# vbus_v2.net
KiCad netlist of a schematic drawn in EAGLE
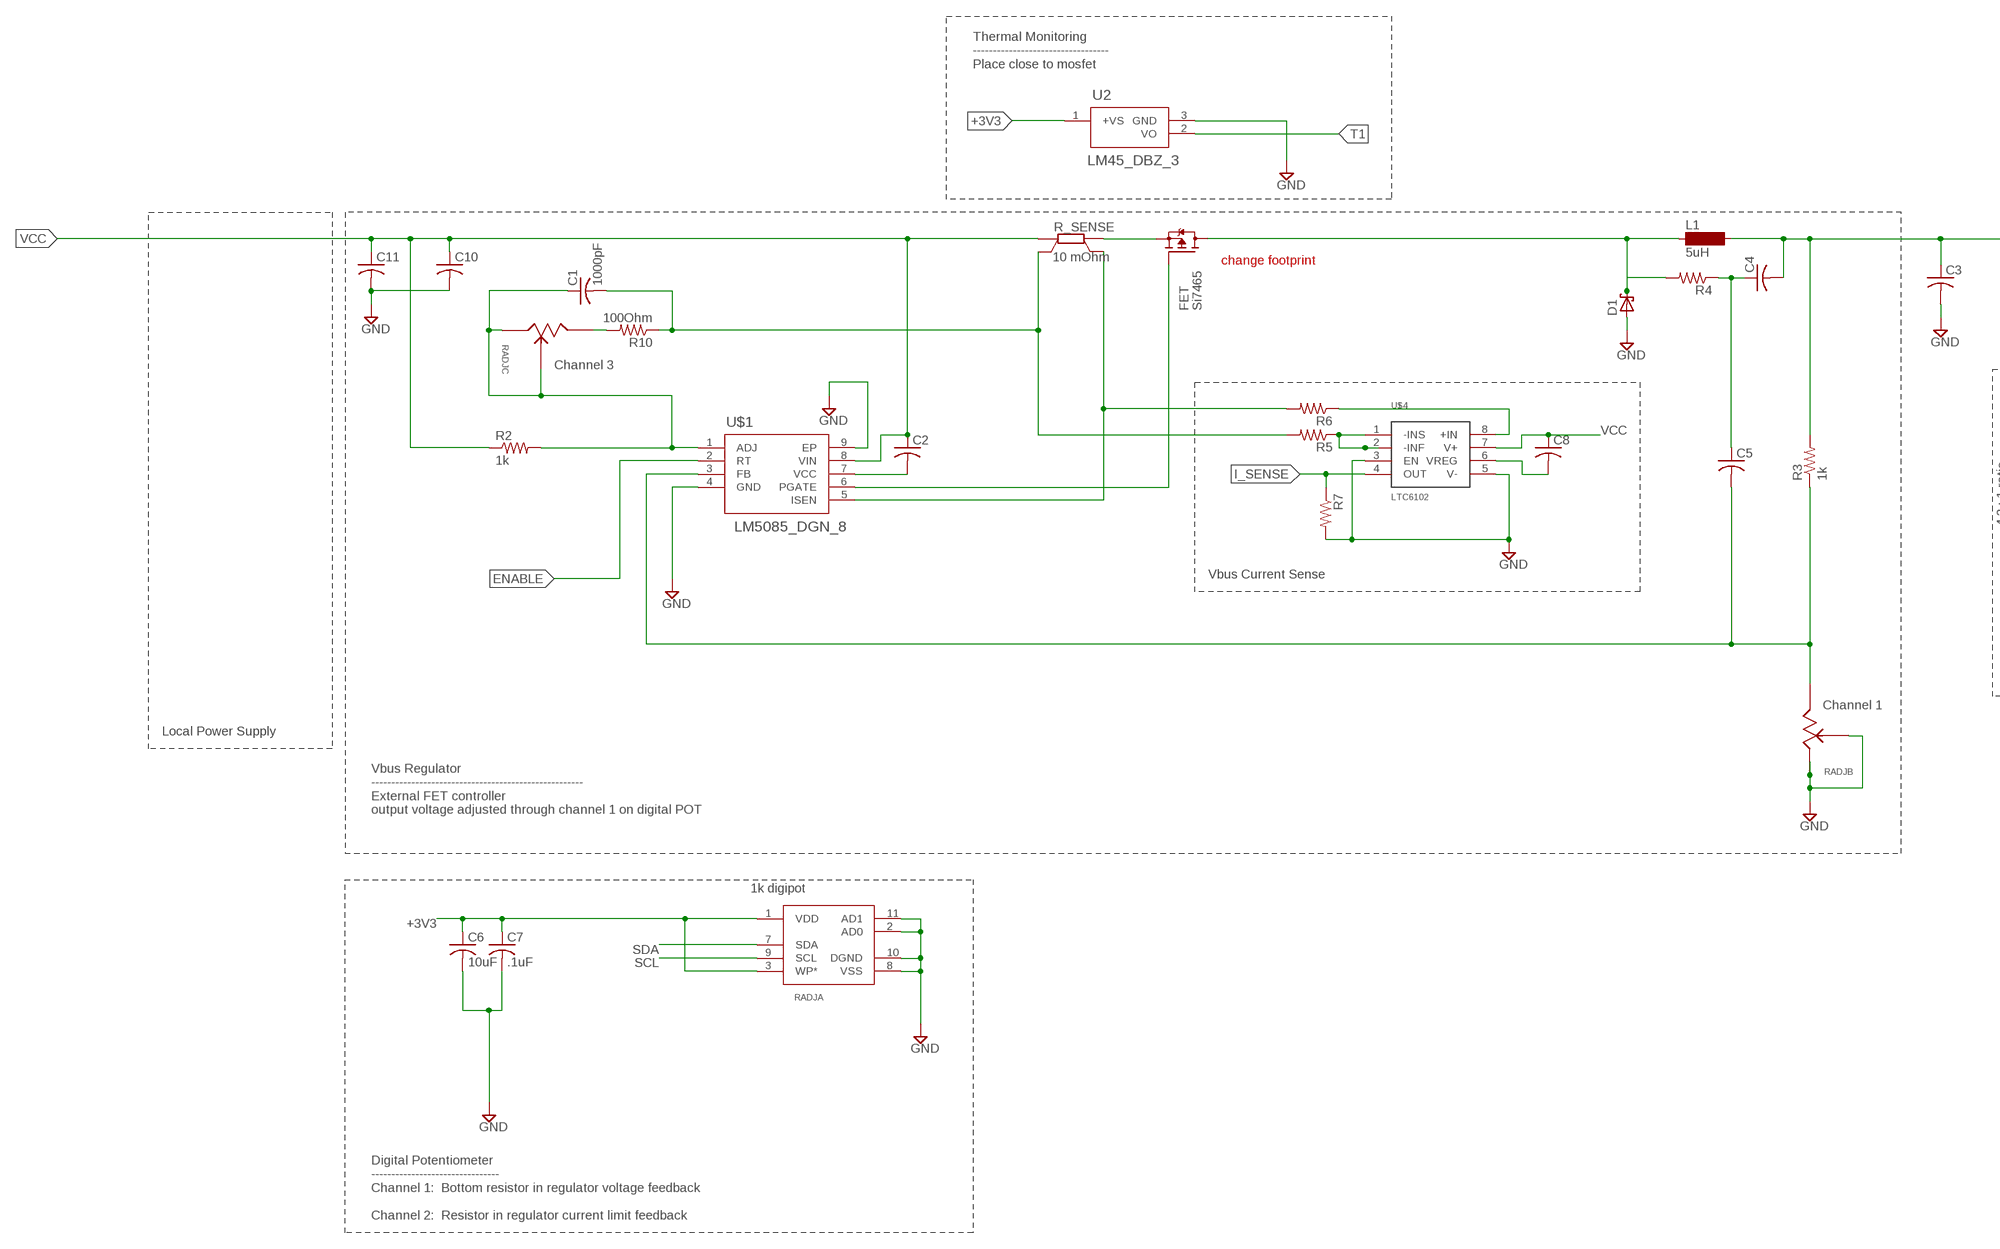
[diagram p0: schematic, sheet 1, part 1 of 2]
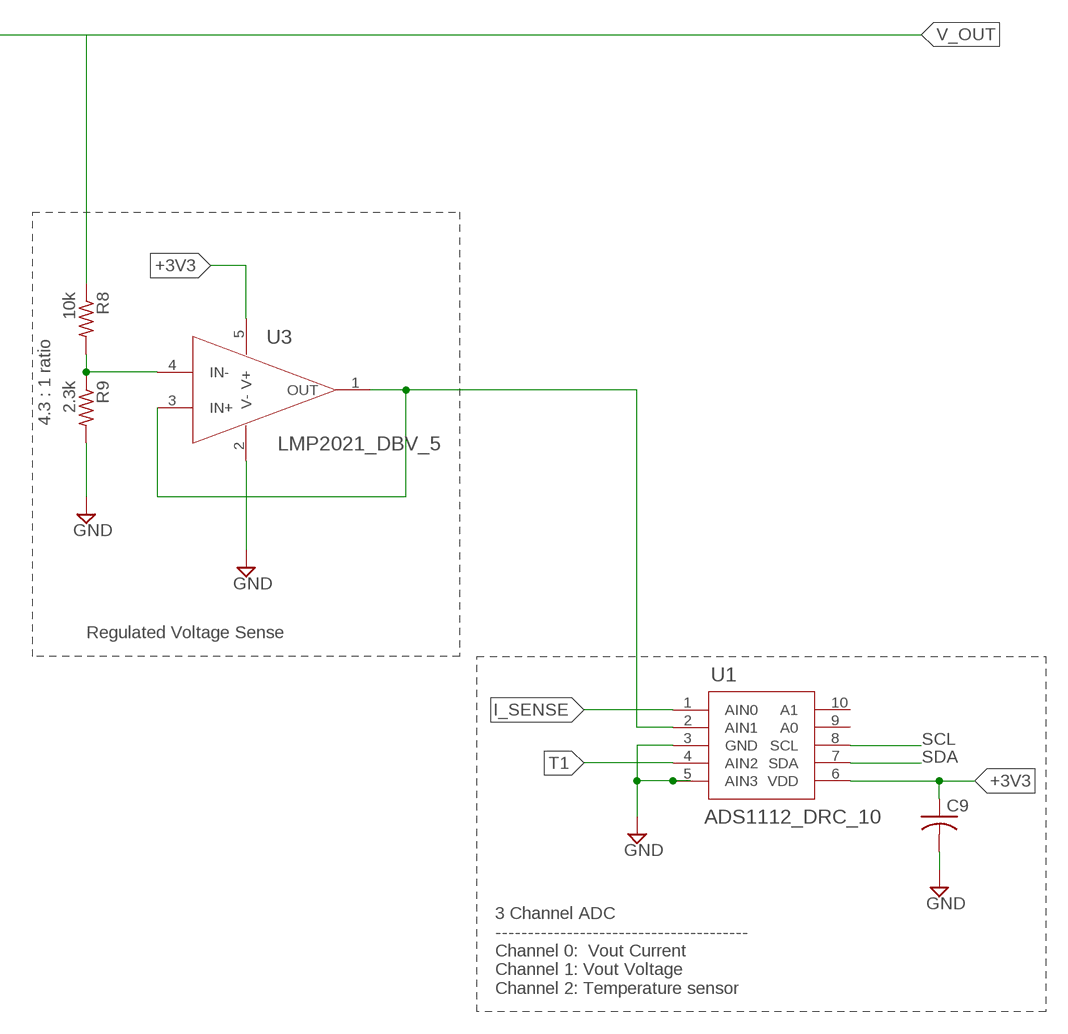
[diagram p1: schematic, sheet 1, part 2 of 2]

(export (version "E")
  (design (tool "Eeschema 10.0.6"))
  (components
    (comp (ref "C1")
      (value "1000pF")
      (footprint "eagle-import:C0805")
      (libsource (lib "eagle-import") (part "C-USC0805"))
    )
    (comp (ref "C2")
      (value "C-USC0805")
      (footprint "eagle-import:C0805")
      (libsource (lib "eagle-import") (part "C-USC0805"))
    )
    (comp (ref "C3")
      (value "C-USC0805")
      (footprint "eagle-import:C0805")
      (libsource (lib "eagle-import") (part "C-USC0805"))
    )
    (comp (ref "C4")
      (value "C-USC0805")
      (footprint "eagle-import:C0805")
      (libsource (lib "eagle-import") (part "C-USC0805"))
    )
    (comp (ref "C5")
      (value "C-USC0805")
      (footprint "eagle-import:C0805")
      (libsource (lib "eagle-import") (part "C-USC0805"))
    )
    (comp (ref "C6")
      (value "10uF")
      (footprint "eagle-import:C0805")
      (libsource (lib "eagle-import") (part "C-USC0805"))
    )
    (comp (ref "C7")
      (value ".1uF")
      (footprint "eagle-import:C0805")
      (libsource (lib "eagle-import") (part "C-USC0805"))
    )
    (comp (ref "C8")
      (value "C-USC0805")
      (footprint "eagle-import:C0805")
      (libsource (lib "eagle-import") (part "C-USC0805"))
    )
    (comp (ref "C9")
      (value "C-USC0805")
      (footprint "eagle-import:C0805")
      (libsource (lib "eagle-import") (part "C-USC0805"))
    )
    (comp (ref "C10")
      (value "C-USC0805")
      (footprint "eagle-import:C0805")
      (libsource (lib "eagle-import") (part "C-USC0805"))
    )
    (comp (ref "C11")
      (value "C-USC0805")
      (footprint "eagle-import:C0805")
      (libsource (lib "eagle-import") (part "C-USC0805"))
    )
    (comp (ref "D1")
      (value "SCHOTTKY-DIODETO92H")
      (footprint "eagle-import:TO92H")
      (libsource (lib "eagle-import") (part "SCHOTTKY-DIODETO92H"))
    )
    (comp (ref "FET")
      (value "Si7465")
      (footprint "eagle-import:SOT-223")
      (libsource (lib "eagle-import") (part "FDT434P"))
    )
    (comp (ref "L1")
      (value "5uH")
      (footprint "eagle-import:MS50")
      (libsource (lib "eagle-import") (part "MS50"))
    )
    (comp (ref "R2")
      (value "1k")
      (footprint "eagle-import:M0805")
      (libsource (lib "eagle-import") (part "R-US_M0805"))
    )
    (comp (ref "R3")
      (value "1k")
      (footprint "eagle-import:M0805")
      (libsource (lib "eagle-import") (part "R-US_M0805"))
    )
    (comp (ref "R4")
      (value "R-US_M0805")
      (footprint "eagle-import:M0805")
      (libsource (lib "eagle-import") (part "R-US_M0805"))
    )
    (comp (ref "R5")
      (value "R-US_M0805")
      (footprint "eagle-import:M0805")
      (libsource (lib "eagle-import") (part "R-US_M0805"))
    )
    (comp (ref "R6")
      (value "R-US_M0805")
      (footprint "eagle-import:M0805")
      (libsource (lib "eagle-import") (part "R-US_M0805"))
    )
    (comp (ref "R7")
      (value "R-US_M0805")
      (footprint "eagle-import:M0805")
      (libsource (lib "eagle-import") (part "R-US_M0805"))
    )
    (comp (ref "R8")
      (value "10k")
      (footprint "eagle-import:M0805")
      (libsource (lib "eagle-import") (part "R-US_M0805"))
    )
    (comp (ref "R9")
      (value "2.3k")
      (footprint "eagle-import:M0805")
      (libsource (lib "eagle-import") (part "R-US_M0805"))
    )
    (comp (ref "R10")
      (value "100Ohm")
      (footprint "eagle-import:M0805")
      (libsource (lib "eagle-import") (part "R-US_M0805"))
    )
    (comp (ref "RADJ")
      (value "AD5252")
      (footprint "eagle-import:RU_14")
      (libsource (lib "eagle-import") (part "AD5252"))
    )
    (comp (ref "R_SENSE")
      (value "10 mOhm")
      (footprint "eagle-import:SMV")
      (libsource (lib "eagle-import") (part "SMV"))
    )
    (comp (ref "U$1")
      (value "LM5085_DGN_8")
      (footprint "eagle-import:MUY08A")
      (fields (field (name "MANUFACTURER_PART_NUMBER") "lm5085mynopb"))
      (libsource (lib "eagle-import") (part "LM5085_DGN_8"))
    )
    (comp (ref "U$4")
      (value "LTC6102")
      (footprint "eagle-import:MS8")
      (libsource (lib "eagle-import") (part "LTC6102"))
    )
    (comp (ref "U1")
      (value "ADS1112_DRC_10")
      (footprint "eagle-import:DG6-10")
      (libsource (lib "eagle-import") (part "ADS1112_DRC_10"))
    )
    (comp (ref "U2")
      (value "LM45_DBZ_3")
      (footprint "eagle-import:MF03A")
      (fields (field (name "PARTNUMBER") "LM45BIM3"))
      (libsource (lib "eagle-import") (part "LM45_DBZ_3"))
    )
    (comp (ref "U3")
      (value "LMP2021_DBV_5")
      (footprint "eagle-import:MF05A")
      (libsource (lib "eagle-import") (part "LMP2021_DBV_5"))
    )
  )
  (nets
    (net (code "1") (name "+3V3") (class "Default")
      (node (ref "C6") (pin "1") (pinfunction "1_1") (pintype "passive"))
      (node (ref "C7") (pin "1") (pinfunction "1_1") (pintype "passive"))
      (node (ref "C9") (pin "1") (pinfunction "1_1") (pintype "passive"))
      (node (ref "RADJ") (pin "1") (pinfunction "VDD_1") (pintype "power_in"))
      (node (ref "RADJ") (pin "3") (pinfunction "WP*_3") (pintype "passive"))
      (node (ref "U1") (pin "6") (pinfunction "VDD_6") (pintype "power_in"))
      (node (ref "U2") (pin "1") (pinfunction "+VS_1") (pintype "input"))
      (node (ref "U3") (pin "5") (pinfunction "V+_5") (pintype "power_in"))
    )
    (net (code "2") (name "/SCL") (class "Default")
      (node (ref "RADJ") (pin "9") (pinfunction "SCL_9") (pintype "passive"))
      (node (ref "U1") (pin "8") (pinfunction "SCL_8") (pintype "output"))
    )
    (net (code "3") (name "/SDA") (class "Default")
      (node (ref "RADJ") (pin "7") (pinfunction "SDA_7") (pintype "passive"))
      (node (ref "U1") (pin "7") (pinfunction "SDA_7") (pintype "passive"))
    )
    (net (code "4") (name "ENABLE") (class "Default")
      (node (ref "U$1") (pin "2") (pinfunction "RT_2") (pintype "passive"))
    )
    (net (code "5") (name "GND") (class "Default")
      (node (ref "C10") (pin "2") (pinfunction "2_2") (pintype "passive"))
      (node (ref "C11") (pin "2") (pinfunction "2_2") (pintype "passive"))
      (node (ref "C3") (pin "2") (pinfunction "2_2") (pintype "passive"))
      (node (ref "C6") (pin "2") (pinfunction "2_2") (pintype "passive"))
      (node (ref "C7") (pin "2") (pinfunction "2_2") (pintype "passive"))
      (node (ref "C9") (pin "2") (pinfunction "2_2") (pintype "passive"))
      (node (ref "D1") (pin "1") (pinfunction "A_1") (pintype "passive"))
      (node (ref "R7") (pin "2") (pinfunction "2_2") (pintype "passive"))
      (node (ref "R9") (pin "2") (pinfunction "2_2") (pintype "passive"))
      (node (ref "RADJ") (pin "10") (pinfunction "DGND_10") (pintype "passive"))
      (node (ref "RADJ") (pin "11") (pinfunction "AD1_11") (pintype "passive"))
      (node (ref "RADJ") (pin "2") (pinfunction "AD0_2") (pintype "passive"))
      (node (ref "RADJ") (pin "4") (pinfunction "W1_4") (pintype "passive"))
      (node (ref "RADJ") (pin "5") (pinfunction "B1_5") (pintype "passive"))
      (node (ref "RADJ") (pin "8") (pinfunction "VSS_8") (pintype "power_in"))
      (node (ref "U$1") (pin "4") (pinfunction "GND_4") (pintype "power_in"))
      (node (ref "U$1") (pin "9") (pinfunction "EP_9") (pintype "passive"))
      (node (ref "U$4") (pin "3") (pinfunction "EN_3") (pintype "power_in"))
      (node (ref "U$4") (pin "5") (pinfunction "V-_5") (pintype "power_in"))
      (node (ref "U1") (pin "3") (pinfunction "GND_3") (pintype "power_in"))
      (node (ref "U1") (pin "5") (pinfunction "AIN3_5") (pintype "input"))
      (node (ref "U2") (pin "3") (pinfunction "GND_3") (pintype "passive"))
      (node (ref "U3") (pin "2") (pinfunction "V-_2") (pintype "power_in"))
    )
    (net (code "6") (name "I_SENSE") (class "Default")
      (node (ref "R7") (pin "1") (pinfunction "1_1") (pintype "passive"))
      (node (ref "U$4") (pin "4") (pinfunction "OUT_4") (pintype "power_in"))
      (node (ref "U1") (pin "1") (pinfunction "AIN0_1") (pintype "input"))
    )
    (net (code "7") (name "Net-(C4-Pad1)") (class "Default")
      (node (ref "C4") (pin "1") (pinfunction "1_1") (pintype "passive"))
      (node (ref "C5") (pin "1") (pinfunction "1_1") (pintype "passive"))
      (node (ref "R4") (pin "1") (pinfunction "1_1") (pintype "passive"))
    )
    (net (code "8") (name "Net-(D1-C)") (class "Default")
      (node (ref "D1") (pin "2") (pinfunction "C_2") (pintype "passive"))
      (node (ref "FET") (pin "2") (pinfunction "D_2") (pintype "passive"))
      (node (ref "FET") (pin "4") (pinfunction "D_4") (pintype "passive"))
      (node (ref "L1") (pin "1") (pinfunction "1_1") (pintype "passive"))
      (node (ref "R4") (pin "2") (pinfunction "2_2") (pintype "passive"))
    )
    (net (code "9") (name "Net-(FET-G)") (class "Default")
      (node (ref "FET") (pin "1") (pinfunction "G_1") (pintype "passive"))
      (node (ref "U$1") (pin "6") (pinfunction "PGATE_6") (pintype "passive"))
    )
    (net (code "10") (name "Net-(FET-S)") (class "Default")
      (node (ref "FET") (pin "3") (pinfunction "S_3") (pintype "passive"))
      (node (ref "R_SENSE") (pin "I1") (pinfunction "A_I1") (pintype "passive"))
    )
    (net (code "11") (name "Net-(RADJB-A1)") (class "Default")
      (node (ref "C5") (pin "2") (pinfunction "2_2") (pintype "passive"))
      (node (ref "R3") (pin "1") (pinfunction "1_1") (pintype "passive"))
      (node (ref "RADJ") (pin "6") (pinfunction "A1_6") (pintype "passive"))
      (node (ref "U$1") (pin "3") (pinfunction "FB_3") (pintype "passive"))
    )
    (net (code "12") (name "Net-(RADJC-A1)") (class "Default")
      (node (ref "R10") (pin "2") (pinfunction "2_2") (pintype "passive"))
      (node (ref "RADJ") (pin "12") (pinfunction "A1_12") (pintype "passive"))
    )
    (net (code "13") (name "Net-(RADJC-B1)") (class "Default")
      (node (ref "C1") (pin "1") (pinfunction "1_1") (pintype "passive"))
      (node (ref "R2") (pin "2") (pinfunction "2_2") (pintype "passive"))
      (node (ref "RADJ") (pin "13") (pinfunction "B1_13") (pintype "passive"))
      (node (ref "RADJ") (pin "14") (pinfunction "W1_14") (pintype "passive"))
      (node (ref "U$1") (pin "1") (pinfunction "ADJ_1") (pintype "passive"))
    )
    (net (code "14") (name "Net-(R_SENSE-SA)") (class "Default")
      (node (ref "R6") (pin "2") (pinfunction "2_2") (pintype "passive"))
      (node (ref "R_SENSE") (pin "U1") (pinfunction "SA_U1") (pintype "passive"))
      (node (ref "U$1") (pin "5") (pinfunction "ISEN_5") (pintype "passive"))
    )
    (net (code "15") (name "Net-(R_SENSE-SB)") (class "Default")
      (node (ref "C1") (pin "2") (pinfunction "2_2") (pintype "passive"))
      (node (ref "R10") (pin "1") (pinfunction "1_1") (pintype "passive"))
      (node (ref "R5") (pin "2") (pinfunction "2_2") (pintype "passive"))
      (node (ref "R_SENSE") (pin "U2") (pinfunction "SB_U2") (pintype "passive"))
    )
    (net (code "16") (name "Net-(U$1-VCC)") (class "Default")
      (node (ref "C2") (pin "2") (pinfunction "2_2") (pintype "passive"))
      (node (ref "U$1") (pin "7") (pinfunction "VCC_7") (pintype "power_in"))
    )
    (net (code "17") (name "Net-(U$4-+IN)") (class "Default")
      (node (ref "R6") (pin "1") (pinfunction "1_1") (pintype "passive"))
      (node (ref "U$4") (pin "8") (pinfunction "+IN_8") (pintype "power_in"))
    )
    (net (code "18") (name "Net-(U$4--INF)") (class "Default")
      (node (ref "R5") (pin "1") (pinfunction "1_1") (pintype "passive"))
      (node (ref "U$4") (pin "1") (pinfunction "-INS_1") (pintype "power_in"))
      (node (ref "U$4") (pin "2") (pinfunction "-INF_2") (pintype "power_in"))
    )
    (net (code "19") (name "Net-(U$4-VREG)") (class "Default")
      (node (ref "C8") (pin "2") (pinfunction "2_2") (pintype "passive"))
      (node (ref "U$4") (pin "6") (pinfunction "VREG_6") (pintype "power_in"))
    )
    (net (code "20") (name "Net-(U1-AIN1)") (class "Default")
      (node (ref "U1") (pin "2") (pinfunction "AIN1_2") (pintype "input"))
      (node (ref "U3") (pin "1") (pinfunction "OUT_1") (pintype "output"))
      (node (ref "U3") (pin "3") (pinfunction "IN+_3") (pintype "input"))
    )
    (net (code "21") (name "Net-(U3-IN-)") (class "Default")
      (node (ref "R8") (pin "2") (pinfunction "2_2") (pintype "passive"))
      (node (ref "R9") (pin "1") (pinfunction "1_1") (pintype "passive"))
      (node (ref "U3") (pin "4") (pinfunction "IN-_4") (pintype "input"))
    )
    (net (code "22") (name "T1") (class "Default")
      (node (ref "U1") (pin "4") (pinfunction "AIN2_4") (pintype "input"))
      (node (ref "U2") (pin "2") (pinfunction "VO_2") (pintype "output"))
    )
    (net (code "23") (name "VCC") (class "Default")
      (node (ref "C10") (pin "1") (pinfunction "1_1") (pintype "passive"))
      (node (ref "C11") (pin "1") (pinfunction "1_1") (pintype "passive"))
      (node (ref "C2") (pin "1") (pinfunction "1_1") (pintype "passive"))
      (node (ref "C8") (pin "1") (pinfunction "1_1") (pintype "passive"))
      (node (ref "R2") (pin "1") (pinfunction "1_1") (pintype "passive"))
      (node (ref "R_SENSE") (pin "I2") (pinfunction "B_I2") (pintype "passive"))
      (node (ref "U$1") (pin "8") (pinfunction "VIN_8") (pintype "passive"))
      (node (ref "U$4") (pin "7") (pinfunction "V+_7") (pintype "power_in"))
    )
    (net (code "24") (name "V_OUT") (class "Default")
      (node (ref "C3") (pin "1") (pinfunction "1_1") (pintype "passive"))
      (node (ref "C4") (pin "2") (pinfunction "2_2") (pintype "passive"))
      (node (ref "L1") (pin "2") (pinfunction "2_2") (pintype "passive"))
      (node (ref "R3") (pin "2") (pinfunction "2_2") (pintype "passive"))
      (node (ref "R8") (pin "1") (pinfunction "1_1") (pintype "passive"))
    )
    (net (code "25") (name "unconnected-(U1-A0-Pad9)") (class "Default")
      (node (ref "U1") (pin "9") (pinfunction "A0_9") (pintype "passive"))
    )
    (net (code "26") (name "unconnected-(U1-A1-Pad10)") (class "Default")
      (node (ref "U1") (pin "10") (pinfunction "A1_10") (pintype "passive"))
    )
  )
)
